# Zynq_processing_system.net
KiCad netlist of a schematic drawn in Altium Designer
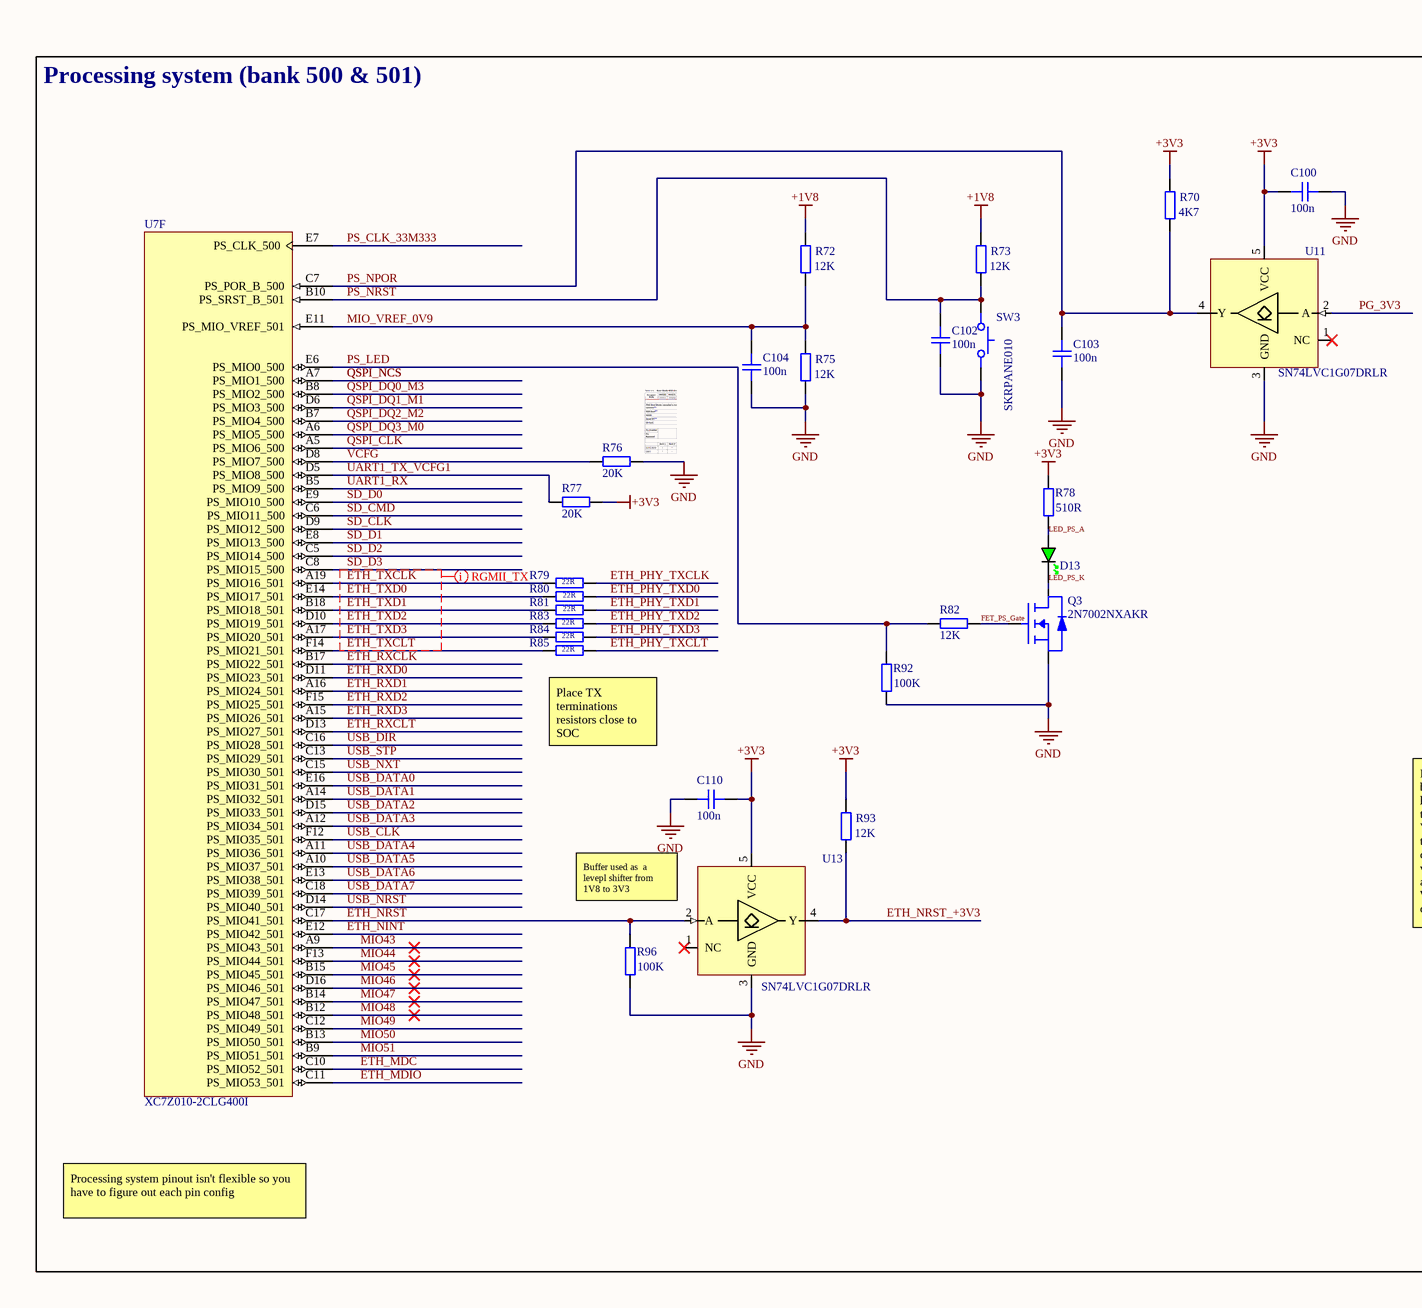
[diagram p0: Zynq processing system (PS).SchDoc, left]
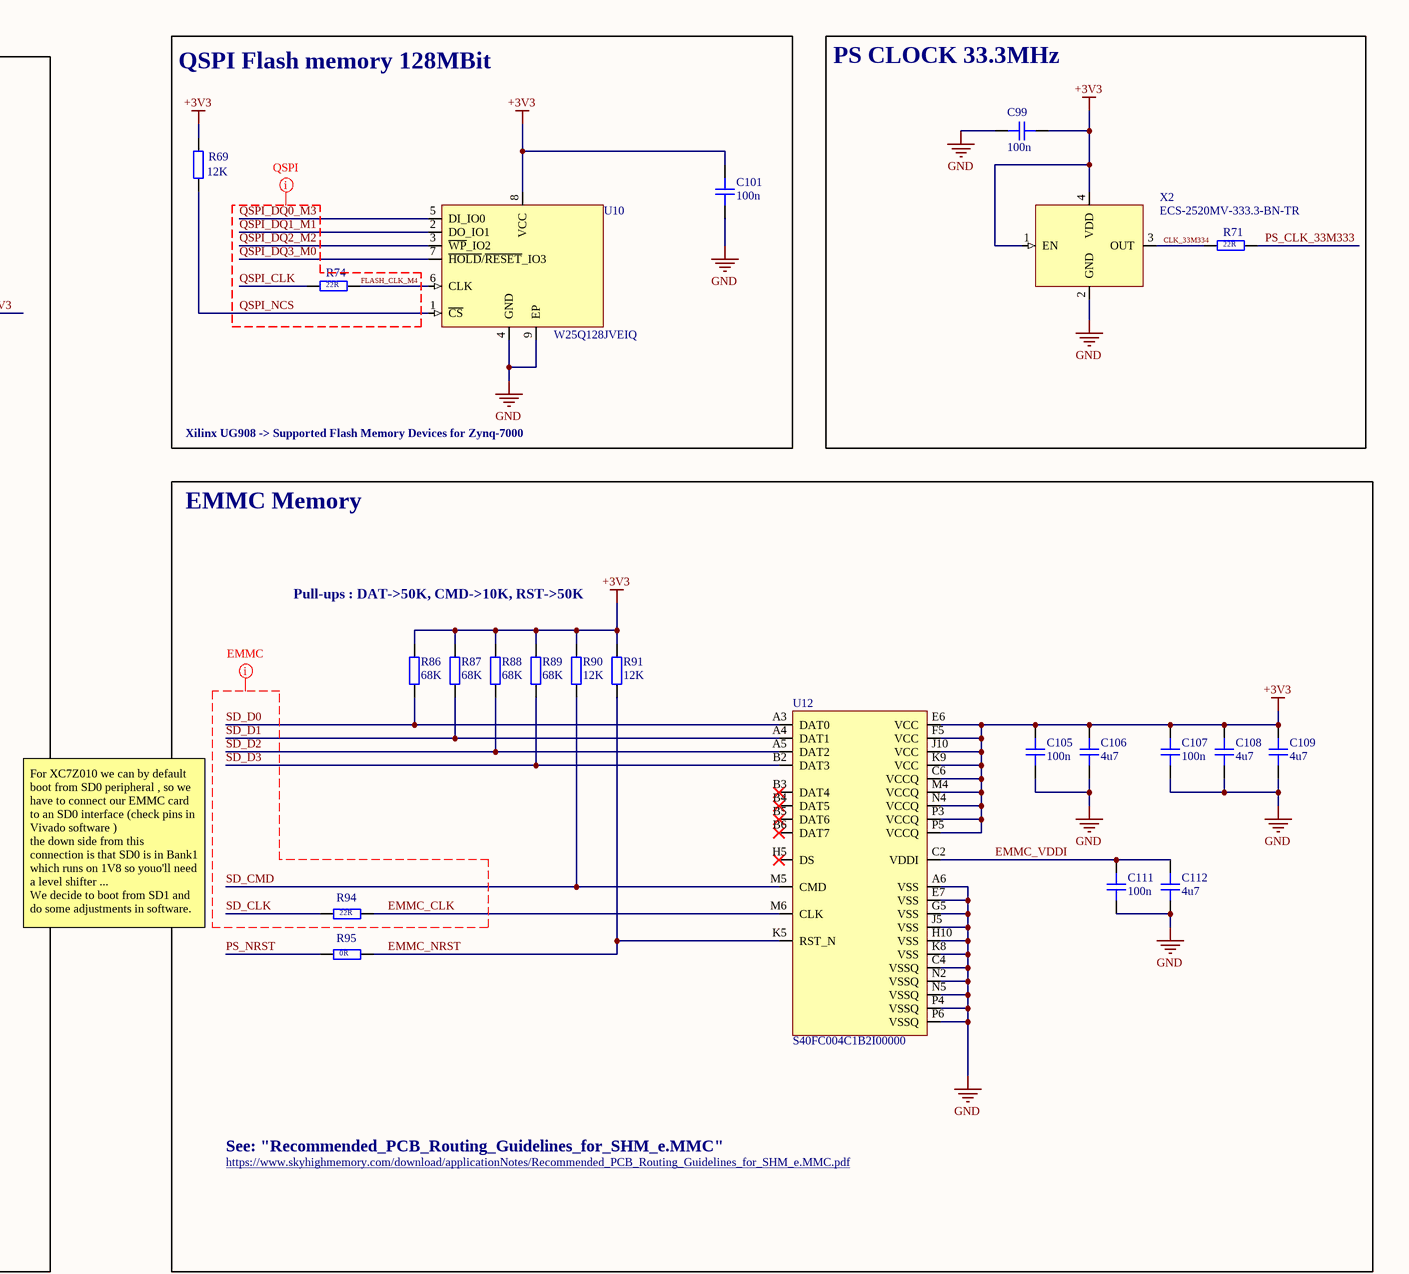
[diagram p1: Zynq processing system (PS).SchDoc, right]

(export (version "E")
  (design (tool "Eeschema 10.0.6"))
  (components
    (comp (ref "C99")
      (value "100n")
      (footprint "CAP_0402")
      (description "Capacitor SMD 0402")
      (libsource (lib "Schematic-Lib-PhilsLab") (part "CAP_0402"))
    )
    (comp (ref "C100")
      (value "100n")
      (footprint "CAP_0402")
      (description "Capacitor SMD 0402")
      (libsource (lib "Schematic-Lib-PhilsLab") (part "CAP_0402"))
    )
    (comp (ref "C101")
      (value "100n")
      (footprint "CAP_0402")
      (description "Capacitor SMD 0402")
      (libsource (lib "Schematic-Lib-PhilsLab") (part "CAP_0402"))
    )
    (comp (ref "C102")
      (value "100n")
      (footprint "CAP_0402")
      (description "Capacitor SMD 0402")
      (libsource (lib "Schematic-Lib-PhilsLab") (part "CAP_0402"))
    )
    (comp (ref "C103")
      (value "100n")
      (footprint "CAP_0402")
      (description "Capacitor SMD 0402")
      (libsource (lib "Schematic-Lib-PhilsLab") (part "CAP_0402"))
    )
    (comp (ref "C104")
      (value "100n")
      (footprint "CAP_0402")
      (description "Capacitor SMD 0402")
      (libsource (lib "Schematic-Lib-PhilsLab") (part "CAP_0402"))
    )
    (comp (ref "C105")
      (value "100n")
      (footprint "CAP_0402")
      (description "Capacitor SMD 0402")
      (libsource (lib "Schematic-Lib-PhilsLab") (part "CAP_0402"))
    )
    (comp (ref "C106")
      (value "4u7")
      (footprint "CAP_0402")
      (description "Capacitor SMD 0402")
      (libsource (lib "Schematic-Lib-PhilsLab") (part "CAP_0402"))
    )
    (comp (ref "C107")
      (value "100n")
      (footprint "CAP_0402")
      (description "Capacitor SMD 0402")
      (libsource (lib "Schematic-Lib-PhilsLab") (part "CAP_0402"))
    )
    (comp (ref "C108")
      (value "4u7")
      (footprint "CAP_0402")
      (description "Capacitor SMD 0402")
      (libsource (lib "Schematic-Lib-PhilsLab") (part "CAP_0402"))
    )
    (comp (ref "C109")
      (value "4u7")
      (footprint "CAP_0402")
      (description "Capacitor SMD 0402")
      (libsource (lib "Schematic-Lib-PhilsLab") (part "CAP_0402"))
    )
    (comp (ref "C110")
      (value "100n")
      (footprint "CAP_0402")
      (description "Capacitor SMD 0402")
      (libsource (lib "Schematic-Lib-PhilsLab") (part "CAP_0402"))
    )
    (comp (ref "C111")
      (value "100n")
      (footprint "CAP_0402")
      (description "Capacitor SMD 0402")
      (libsource (lib "Schematic-Lib-PhilsLab") (part "CAP_0402"))
    )
    (comp (ref "C112")
      (value "4u7")
      (footprint "CAP_0402")
      (description "Capacitor SMD 0402")
      (libsource (lib "Schematic-Lib-PhilsLab") (part "CAP_0402"))
    )
    (comp (ref "D13")
      (value "GREEN")
      (footprint "LED_0402_GREEN")
      (description "LED 0402 GREEN SMD")
      (libsource (lib "Schematic-Lib-PhilsLab") (part "LED_0402_GREEN"))
    )
    (comp (ref "Q3")
      (value "2N7002NXAKR")
      (footprint "SSM3J338R,LF-SOT23-F")
      (description "MOSFET N-Channel Vds=60V Id=300mA with ESD Protection")
      (fields (field (name "MANUFACTURER") "Nexperia"))
      (libsource (lib "Schematic-Lib-PhilsLab") (part "2N7002NXAKR"))
    )
    (comp (ref "R69")
      (value "12K")
      (footprint "RES_0402")
      (description "Resistor SMD 0402")
      (fields (field (name "Comment") "R0402"))
      (libsource (lib "Schematic-Lib-PhilsLab") (part "RES_0402"))
    )
    (comp (ref "R70")
      (value "4K7")
      (footprint "RES_0402")
      (description "Resistor SMD 0402")
      (fields (field (name "Comment") "R0402"))
      (libsource (lib "Schematic-Lib-PhilsLab") (part "RES_0402"))
    )
    (comp (ref "R71")
      (value "22R")
      (footprint "RES_0402")
      (description "Resistor SMD 0402")
      (fields (field (name "Comment") "R0402"))
      (libsource (lib "Schematic-Lib-PhilsLab") (part "RES_0402"))
    )
    (comp (ref "R72")
      (value "12K")
      (footprint "RES_0402")
      (description "Resistor SMD 0402")
      (fields (field (name "Comment") "R0402"))
      (libsource (lib "Schematic-Lib-PhilsLab") (part "RES_0402"))
    )
    (comp (ref "R73")
      (value "12K")
      (footprint "RES_0402")
      (description "Resistor SMD 0402")
      (fields (field (name "Comment") "R0402"))
      (libsource (lib "Schematic-Lib-PhilsLab") (part "RES_0402"))
    )
    (comp (ref "R74")
      (value "22R")
      (footprint "RES_0402")
      (description "Resistor SMD 0402")
      (fields (field (name "Comment") "R0402"))
      (libsource (lib "Schematic-Lib-PhilsLab") (part "RES_0402"))
    )
    (comp (ref "R75")
      (value "12K")
      (footprint "RES_0402")
      (description "Resistor SMD 0402")
      (fields (field (name "Comment") "R0402"))
      (libsource (lib "Schematic-Lib-PhilsLab") (part "RES_0402"))
    )
    (comp (ref "R76")
      (value "20K")
      (footprint "RES_0402")
      (description "Resistor SMD 0402")
      (fields (field (name "Comment") "R0402"))
      (libsource (lib "Schematic-Lib-PhilsLab") (part "RES_0402"))
    )
    (comp (ref "R77")
      (value "20K")
      (footprint "RES_0402")
      (description "Resistor SMD 0402")
      (fields (field (name "Comment") "R0402"))
      (libsource (lib "Schematic-Lib-PhilsLab") (part "RES_0402"))
    )
    (comp (ref "R78")
      (value "510R")
      (footprint "RES_0402")
      (description "Resistor SMD 0402")
      (fields (field (name "Comment") "R0402"))
      (libsource (lib "Schematic-Lib-PhilsLab") (part "RES_0402"))
    )
    (comp (ref "R79")
      (value "22R")
      (footprint "RES_0402")
      (description "Resistor SMD 0402")
      (fields (field (name "Comment") "R0402"))
      (libsource (lib "Schematic-Lib-PhilsLab") (part "RES_0402"))
    )
    (comp (ref "R80")
      (value "22R")
      (footprint "RES_0402")
      (description "Resistor SMD 0402")
      (fields (field (name "Comment") "R0402"))
      (libsource (lib "Schematic-Lib-PhilsLab") (part "RES_0402"))
    )
    (comp (ref "R81")
      (value "22R")
      (footprint "RES_0402")
      (description "Resistor SMD 0402")
      (fields (field (name "Comment") "R0402"))
      (libsource (lib "Schematic-Lib-PhilsLab") (part "RES_0402"))
    )
    (comp (ref "R82")
      (value "12K")
      (footprint "RES_0402")
      (description "Resistor SMD 0402")
      (fields (field (name "Comment") "R0402"))
      (libsource (lib "Schematic-Lib-PhilsLab") (part "RES_0402"))
    )
    (comp (ref "R83")
      (value "22R")
      (footprint "RES_0402")
      (description "Resistor SMD 0402")
      (fields (field (name "Comment") "R0402"))
      (libsource (lib "Schematic-Lib-PhilsLab") (part "RES_0402"))
    )
    (comp (ref "R84")
      (value "22R")
      (footprint "RES_0402")
      (description "Resistor SMD 0402")
      (fields (field (name "Comment") "R0402"))
      (libsource (lib "Schematic-Lib-PhilsLab") (part "RES_0402"))
    )
    (comp (ref "R85")
      (value "22R")
      (footprint "RES_0402")
      (description "Resistor SMD 0402")
      (fields (field (name "Comment") "R0402"))
      (libsource (lib "Schematic-Lib-PhilsLab") (part "RES_0402"))
    )
    (comp (ref "R86")
      (value "68K")
      (footprint "RES_0402")
      (description "Resistor SMD 0402")
      (fields (field (name "Comment") "R0402"))
      (libsource (lib "Schematic-Lib-PhilsLab") (part "RES_0402"))
    )
    (comp (ref "R87")
      (value "68K")
      (footprint "RES_0402")
      (description "Resistor SMD 0402")
      (fields (field (name "Comment") "R0402"))
      (libsource (lib "Schematic-Lib-PhilsLab") (part "RES_0402"))
    )
    (comp (ref "R88")
      (value "68K")
      (footprint "RES_0402")
      (description "Resistor SMD 0402")
      (fields (field (name "Comment") "R0402"))
      (libsource (lib "Schematic-Lib-PhilsLab") (part "RES_0402"))
    )
    (comp (ref "R89")
      (value "68K")
      (footprint "RES_0402")
      (description "Resistor SMD 0402")
      (fields (field (name "Comment") "R0402"))
      (libsource (lib "Schematic-Lib-PhilsLab") (part "RES_0402"))
    )
    (comp (ref "R90")
      (value "12K")
      (footprint "RES_0402")
      (description "Resistor SMD 0402")
      (fields (field (name "Comment") "R0402"))
      (libsource (lib "Schematic-Lib-PhilsLab") (part "RES_0402"))
    )
    (comp (ref "R91")
      (value "12K")
      (footprint "RES_0402")
      (description "Resistor SMD 0402")
      (fields (field (name "Comment") "R0402"))
      (libsource (lib "Schematic-Lib-PhilsLab") (part "RES_0402"))
    )
    (comp (ref "R92")
      (value "100K")
      (footprint "RES_0402")
      (description "Resistor SMD 0402")
      (fields (field (name "Comment") "R0402"))
      (libsource (lib "Schematic-Lib-PhilsLab") (part "RES_0402"))
    )
    (comp (ref "R93")
      (value "12K")
      (footprint "RES_0402")
      (description "Resistor SMD 0402")
      (fields (field (name "Comment") "R0402"))
      (libsource (lib "Schematic-Lib-PhilsLab") (part "RES_0402"))
    )
    (comp (ref "R94")
      (value "22R")
      (footprint "RES_0402")
      (description "Resistor SMD 0402")
      (fields (field (name "Comment") "R0402"))
      (libsource (lib "Schematic-Lib-PhilsLab") (part "RES_0402"))
    )
    (comp (ref "R95")
      (value "0R")
      (footprint "RES_0402")
      (description "Resistor SMD 0402")
      (fields (field (name "Comment") "R0402"))
      (libsource (lib "Schematic-Lib-PhilsLab") (part "RES_0402"))
    )
    (comp (ref "R96")
      (value "100K")
      (footprint "RES_0402")
      (description "Resistor SMD 0402")
      (fields (field (name "Comment") "R0402"))
      (libsource (lib "Schematic-Lib-PhilsLab") (part "RES_0402"))
    )
    (comp (ref "SW3")
      (value "SKRPANE010")
      (footprint "SKRPANE010")
      (description "Tactile Switch SMD SPST")
      (fields (field (name "MANUFACTURER") "Alps Alpine"))
      (libsource (lib "Schematic-Lib-PhilsLab") (part "SKRPANE010"))
    )
    (comp (ref "U7")
      (value "XC7Z010-2CLG400I")
      (footprint "BGA400C80P20X20_1700X1700X160N")
      (libsource (lib "Zynq_SOM") (part "XC7Z010-2CLG400I"))
    )
    (comp (ref "U10")
      (value "W25Q128JVEIQ")
      (footprint "WSON-8-8X6")
      (description "3V 128M-BIT SERIAL FLASH MEMORY WITH DUAL/QUAD SPI & QPI & DTR WSON-8")
      (fields (field (name "MANUFACTURER") "Winbond"))
      (libsource (lib "Schematic-Lib-PhilsLab") (part "W25Q128JVEIQ"))
    )
    (comp (ref "U11")
      (value "SN74LVC1G07DRLR")
      (footprint "SOT-5")
      (description "Single Buffer/Driver With Open-Drain Output")
      (fields (field (name "MANUFACTURER") "Texas Instruments"))
      (libsource (lib "Schematic-Lib-PhilsLab") (part "SN74LVC1G07DRLR"))
    )
    (comp (ref "U12")
      (value "S40FC004C1B2I00000")
      (footprint "VFBGA153-9.0x7.5x0.8")
      (description "eMMC MLC Memory 4GB 3V3")
      (fields (field (name "MANUFACTURER") "SkyHigh Memory"))
      (libsource (lib "Schematic-Lib-PhilsLab") (part "S40FC004C1B2I00000"))
    )
    (comp (ref "U13")
      (value "SN74LVC1G07DRLR")
      (footprint "SOT-5")
      (description "Single Buffer/Driver With Open-Drain Output")
      (fields (field (name "MANUFACTURER") "Texas Instruments"))
      (libsource (lib "") (part "SN74LVC1G07DRLR_1"))
    )
    (comp (ref "X2")
      (value "ECS-2520MV-333.3-BN-TR")
      (footprint "XTAL_2520")
      (fields
        (field (name "MANUFACTURER") "ECS")
        (field (name "MANUFACTURER PART NUMBER") "ECS-2520MV-130-BN-TR")
      )
      (libsource (lib "Schematic-Lib-PhilsLab") (part "ECS-2520MV-130-BN-TR"))
    )
  )
  (nets
    (net (code "1") (name "+1V8") (class "Default")
      (node (ref "R72") (pin "2") (pinfunction "2_2") (pintype "passive"))
      (node (ref "R73") (pin "2") (pinfunction "2_2") (pintype "passive"))
    )
    (net (code "2") (name "+3V3") (class "Default")
      (node (ref "C100") (pin "2") (pinfunction "2_2") (pintype "passive"))
      (node (ref "C101") (pin "1") (pinfunction "1_1") (pintype "passive"))
      (node (ref "C105") (pin "1") (pinfunction "1_1") (pintype "passive"))
      (node (ref "C106") (pin "1") (pinfunction "1_1") (pintype "passive"))
      (node (ref "C107") (pin "1") (pinfunction "1_1") (pintype "passive"))
      (node (ref "C108") (pin "1") (pinfunction "1_1") (pintype "passive"))
      (node (ref "C109") (pin "1") (pinfunction "1_1") (pintype "passive"))
      (node (ref "C110") (pin "2") (pinfunction "2_2") (pintype "passive"))
      (node (ref "C99") (pin "1") (pinfunction "1_1") (pintype "passive"))
      (node (ref "R69") (pin "2") (pinfunction "2_2") (pintype "passive"))
      (node (ref "R70") (pin "2") (pinfunction "2_2") (pintype "passive"))
      (node (ref "R77") (pin "1") (pinfunction "1_1") (pintype "passive"))
      (node (ref "R78") (pin "1") (pinfunction "1_1") (pintype "passive"))
      (node (ref "R86") (pin "1") (pinfunction "1_1") (pintype "passive"))
      (node (ref "R87") (pin "1") (pinfunction "1_1") (pintype "passive"))
      (node (ref "R88") (pin "1") (pinfunction "1_1") (pintype "passive"))
      (node (ref "R89") (pin "1") (pinfunction "1_1") (pintype "passive"))
      (node (ref "R90") (pin "1") (pinfunction "1_1") (pintype "passive"))
      (node (ref "R91") (pin "1") (pinfunction "1_1") (pintype "passive"))
      (node (ref "R93") (pin "2") (pinfunction "2_2") (pintype "passive"))
      (node (ref "U10") (pin "8") (pinfunction "VCC_8") (pintype "power_in"))
      (node (ref "U11") (pin "5") (pinfunction "VCC_5") (pintype "power_in"))
      (node (ref "U12") (pin "C6") (pinfunction "VCCQ_C6") (pintype "passive"))
      (node (ref "U12") (pin "E6") (pinfunction "VCC_E6") (pintype "passive"))
      (node (ref "U12") (pin "F5") (pinfunction "VCC_F5") (pintype "passive"))
      (node (ref "U12") (pin "J10") (pinfunction "VCC_J10") (pintype "passive"))
      (node (ref "U12") (pin "K9") (pinfunction "VCC_K9") (pintype "passive"))
      (node (ref "U12") (pin "M4") (pinfunction "VCCQ_M4") (pintype "passive"))
      (node (ref "U12") (pin "N4") (pinfunction "VCCQ_N4") (pintype "passive"))
      (node (ref "U12") (pin "P3") (pinfunction "VCCQ_P3") (pintype "passive"))
      (node (ref "U12") (pin "P5") (pinfunction "VCCQ_P5") (pintype "passive"))
      (node (ref "U13") (pin "5") (pinfunction "VCC_5") (pintype "power_in"))
      (node (ref "X2") (pin "1") (pinfunction "EN_1") (pintype "input"))
      (node (ref "X2") (pin "4") (pinfunction "VDD_4") (pintype "power_in"))
    )
    (net (code "3") (name "/CLK_33M334") (class "Default")
      (node (ref "R71") (pin "2") (pinfunction "2_2") (pintype "passive"))
      (node (ref "X2") (pin "3") (pinfunction "OUT_3") (pintype "passive"))
    )
    (net (code "4") (name "/EMMC_CLK") (class "Default")
      (node (ref "R94") (pin "1") (pinfunction "1_1") (pintype "passive"))
      (node (ref "U12") (pin "M6") (pinfunction "CLK_M6") (pintype "passive"))
    )
    (net (code "5") (name "/EMMC_NRST") (class "Default")
      (node (ref "R91") (pin "2") (pinfunction "2_2") (pintype "passive"))
      (node (ref "R95") (pin "1") (pinfunction "1_1") (pintype "passive"))
      (node (ref "U12") (pin "K5") (pinfunction "RST_N_K5") (pintype "passive"))
    )
    (net (code "6") (name "/EMMC_VDDI") (class "Default")
      (node (ref "C111") (pin "1") (pinfunction "1_1") (pintype "passive"))
      (node (ref "C112") (pin "1") (pinfunction "1_1") (pintype "passive"))
      (node (ref "U12") (pin "C2") (pinfunction "VDDI_C2") (pintype "passive"))
    )
    (net (code "7") (name "/ETH_MDC") (class "Default")
      (node (ref "U7") (pin "C10") (pinfunction "PS_MIO52_501_C10") (pintype "bidirectional"))
    )
    (net (code "8") (name "/ETH_MDIO") (class "Default")
      (node (ref "U7") (pin "C11") (pinfunction "PS_MIO53_501_C11") (pintype "bidirectional"))
    )
    (net (code "9") (name "/ETH_NINT") (class "Default")
      (node (ref "U7") (pin "E12") (pinfunction "PS_MIO42_501_E12") (pintype "bidirectional"))
    )
    (net (code "10") (name "/ETH_NRST") (class "Default")
      (node (ref "R96") (pin "1") (pinfunction "1_1") (pintype "passive"))
      (node (ref "U13") (pin "2") (pinfunction "A_2") (pintype "input"))
      (node (ref "U7") (pin "C17") (pinfunction "PS_MIO41_501_C17") (pintype "bidirectional"))
    )
    (net (code "11") (name "/ETH_NRST_+3V3") (class "Default")
      (node (ref "R93") (pin "1") (pinfunction "1_1") (pintype "passive"))
      (node (ref "U13") (pin "4") (pinfunction "Y_4") (pintype "open_collector"))
    )
    (net (code "12") (name "/ETH_PHY_TXCLK") (class "Default")
      (node (ref "R79") (pin "1") (pinfunction "1_1") (pintype "passive"))
    )
    (net (code "13") (name "/ETH_PHY_TXCLT") (class "Default")
      (node (ref "R85") (pin "1") (pinfunction "1_1") (pintype "passive"))
    )
    (net (code "14") (name "/ETH_PHY_TXD0") (class "Default")
      (node (ref "R80") (pin "1") (pinfunction "1_1") (pintype "passive"))
    )
    (net (code "15") (name "/ETH_PHY_TXD1") (class "Default")
      (node (ref "R81") (pin "1") (pinfunction "1_1") (pintype "passive"))
    )
    (net (code "16") (name "/ETH_PHY_TXD2") (class "Default")
      (node (ref "R83") (pin "1") (pinfunction "1_1") (pintype "passive"))
    )
    (net (code "17") (name "/ETH_PHY_TXD3") (class "Default")
      (node (ref "R84") (pin "1") (pinfunction "1_1") (pintype "passive"))
    )
    (net (code "18") (name "/ETH_RXCLK") (class "Default")
      (node (ref "U7") (pin "B17") (pinfunction "PS_MIO22_501_B17") (pintype "bidirectional"))
    )
    (net (code "19") (name "/ETH_RXCLT") (class "Default")
      (node (ref "U7") (pin "D13") (pinfunction "PS_MIO27_501_D13") (pintype "bidirectional"))
    )
    (net (code "20") (name "/ETH_RXD0") (class "Default")
      (node (ref "U7") (pin "D11") (pinfunction "PS_MIO23_501_D11") (pintype "bidirectional"))
    )
    (net (code "21") (name "/ETH_RXD1") (class "Default")
      (node (ref "U7") (pin "A16") (pinfunction "PS_MIO24_501_A16") (pintype "bidirectional"))
    )
    (net (code "22") (name "/ETH_RXD2") (class "Default")
      (node (ref "U7") (pin "F15") (pinfunction "PS_MIO25_501_F15") (pintype "bidirectional"))
    )
    (net (code "23") (name "/ETH_RXD3") (class "Default")
      (node (ref "U7") (pin "A15") (pinfunction "PS_MIO26_501_A15") (pintype "bidirectional"))
    )
    (net (code "24") (name "/ETH_TXCLK") (class "Default")
      (node (ref "R79") (pin "2") (pinfunction "2_2") (pintype "passive"))
      (node (ref "U7") (pin "A19") (pinfunction "PS_MIO16_501_A19") (pintype "bidirectional"))
    )
    (net (code "25") (name "/ETH_TXCLT") (class "Default")
      (node (ref "R85") (pin "2") (pinfunction "2_2") (pintype "passive"))
      (node (ref "U7") (pin "F14") (pinfunction "PS_MIO21_501_F14") (pintype "bidirectional"))
    )
    (net (code "26") (name "/ETH_TXD0") (class "Default")
      (node (ref "R80") (pin "2") (pinfunction "2_2") (pintype "passive"))
      (node (ref "U7") (pin "E14") (pinfunction "PS_MIO17_501_E14") (pintype "bidirectional"))
    )
    (net (code "27") (name "/ETH_TXD1") (class "Default")
      (node (ref "R81") (pin "2") (pinfunction "2_2") (pintype "passive"))
      (node (ref "U7") (pin "B18") (pinfunction "PS_MIO18_501_B18") (pintype "bidirectional"))
    )
    (net (code "28") (name "/ETH_TXD2") (class "Default")
      (node (ref "R83") (pin "2") (pinfunction "2_2") (pintype "passive"))
      (node (ref "U7") (pin "D10") (pinfunction "PS_MIO19_501_D10") (pintype "bidirectional"))
    )
    (net (code "29") (name "/ETH_TXD3") (class "Default")
      (node (ref "R84") (pin "2") (pinfunction "2_2") (pintype "passive"))
      (node (ref "U7") (pin "A17") (pinfunction "PS_MIO20_501_A17") (pintype "bidirectional"))
    )
    (net (code "30") (name "/FET_PS_Gate") (class "Default")
      (node (ref "Q3") (pin "G") (pinfunction "G_G") (pintype "passive"))
      (node (ref "R82") (pin "1") (pinfunction "1_1") (pintype "passive"))
    )
    (net (code "31") (name "/FLASH_CLK_M4") (class "Default")
      (node (ref "R74") (pin "1") (pinfunction "1_1") (pintype "passive"))
      (node (ref "U10") (pin "6") (pinfunction "CLK_6") (pintype "input"))
    )
    (net (code "32") (name "/LED_PS_A") (class "Default")
      (node (ref "D13") (pin "A") (pinfunction "A_A") (pintype "passive"))
      (node (ref "R78") (pin "2") (pinfunction "2_2") (pintype "passive"))
    )
    (net (code "33") (name "/LED_PS_K") (class "Default")
      (node (ref "D13") (pin "K") (pinfunction "K_K") (pintype "passive"))
      (node (ref "Q3") (pin "D") (pinfunction "D_D") (pintype "passive"))
    )
    (net (code "34") (name "/MIO43") (class "Default")
      (node (ref "U7") (pin "A9") (pinfunction "PS_MIO43_501_A9") (pintype "bidirectional"))
    )
    (net (code "35") (name "/MIO44") (class "Default")
      (node (ref "U7") (pin "F13") (pinfunction "PS_MIO44_501_F13") (pintype "bidirectional"))
    )
    (net (code "36") (name "/MIO45") (class "Default")
      (node (ref "U7") (pin "B15") (pinfunction "PS_MIO45_501_B15") (pintype "bidirectional"))
    )
    (net (code "37") (name "/MIO46") (class "Default")
      (node (ref "U7") (pin "D16") (pinfunction "PS_MIO46_501_D16") (pintype "bidirectional"))
    )
    (net (code "38") (name "/MIO47") (class "Default")
      (node (ref "U7") (pin "B14") (pinfunction "PS_MIO47_501_B14") (pintype "bidirectional"))
    )
    (net (code "39") (name "/MIO48") (class "Default")
      (node (ref "U7") (pin "B12") (pinfunction "PS_MIO48_501_B12") (pintype "bidirectional"))
    )
    (net (code "40") (name "/MIO49") (class "Default")
      (node (ref "U7") (pin "C12") (pinfunction "PS_MIO49_501_C12") (pintype "bidirectional"))
    )
    (net (code "41") (name "/MIO50") (class "Default")
      (node (ref "U7") (pin "B13") (pinfunction "PS_MIO50_501_B13") (pintype "bidirectional"))
    )
    (net (code "42") (name "/MIO51") (class "Default")
      (node (ref "U7") (pin "B9") (pinfunction "PS_MIO51_501_B9") (pintype "bidirectional"))
    )
    (net (code "43") (name "/MIO_VREF_0V9") (class "Default")
      (node (ref "C104") (pin "1") (pinfunction "1_1") (pintype "passive"))
      (node (ref "R72") (pin "1") (pinfunction "1_1") (pintype "passive"))
      (node (ref "R75") (pin "2") (pinfunction "2_2") (pintype "passive"))
      (node (ref "U7") (pin "E11") (pinfunction "PS_MIO_VREF_501_E11") (pintype "input"))
    )
    (net (code "44") (name "/PG_3V3") (class "Default")
      (node (ref "U11") (pin "2") (pinfunction "A_2") (pintype "input"))
    )
    (net (code "45") (name "/PS_CLK_33M333") (class "Default")
      (node (ref "R71") (pin "1") (pinfunction "1_1") (pintype "passive"))
      (node (ref "U7") (pin "E7") (pinfunction "PS_CLK_500_E7") (pintype "passive"))
    )
    (net (code "46") (name "/PS_LED") (class "Default")
      (node (ref "R82") (pin "2") (pinfunction "2_2") (pintype "passive"))
      (node (ref "R92") (pin "1") (pinfunction "1_1") (pintype "passive"))
      (node (ref "U7") (pin "E6") (pinfunction "PS_MIO0_500_E6") (pintype "bidirectional"))
    )
    (net (code "47") (name "/PS_NPOR") (class "Default")
      (node (ref "C103") (pin "1") (pinfunction "1_1") (pintype "passive"))
      (node (ref "R70") (pin "1") (pinfunction "1_1") (pintype "passive"))
      (node (ref "U11") (pin "4") (pinfunction "Y_4") (pintype "open_collector"))
      (node (ref "U7") (pin "C7") (pinfunction "PS_POR_B_500_C7") (pintype "input"))
    )
    (net (code "48") (name "/PS_NRST") (class "Default")
      (node (ref "C102") (pin "1") (pinfunction "1_1") (pintype "passive"))
      (node (ref "R73") (pin "1") (pinfunction "1_1") (pintype "passive"))
      (node (ref "R95") (pin "2") (pinfunction "2_2") (pintype "passive"))
      (node (ref "SW3") (pin "34") (pintype "passive"))
      (node (ref "U7") (pin "B10") (pinfunction "PS_SRST_B_501_B10") (pintype "input"))
    )
    (net (code "49") (name "/QSPI_CLK") (class "Default")
      (node (ref "R74") (pin "2") (pinfunction "2_2") (pintype "passive"))
      (node (ref "U7") (pin "A5") (pinfunction "PS_MIO6_500_A5") (pintype "bidirectional"))
    )
    (net (code "50") (name "/QSPI_DQ0_M3") (class "Default")
      (node (ref "U10") (pin "5") (pinfunction "DI_IO0_5") (pintype "bidirectional"))
      (node (ref "U7") (pin "B8") (pinfunction "PS_MIO2_500_B8") (pintype "bidirectional"))
    )
    (net (code "51") (name "/QSPI_DQ1_M1") (class "Default")
      (node (ref "U10") (pin "2") (pinfunction "DO_IO1_2") (pintype "bidirectional"))
      (node (ref "U7") (pin "D6") (pinfunction "PS_MIO3_500_D6") (pintype "bidirectional"))
    )
    (net (code "52") (name "/QSPI_DQ2_M2") (class "Default")
      (node (ref "U10") (pin "3") (pinfunction "~{WP}_IO2_3") (pintype "bidirectional"))
      (node (ref "U7") (pin "B7") (pinfunction "PS_MIO4_500_B7") (pintype "bidirectional"))
    )
    (net (code "53") (name "/QSPI_DQ3_M0") (class "Default")
      (node (ref "U10") (pin "7") (pinfunction "~{HOLD}/~{RESET}_IO3_7") (pintype "bidirectional"))
      (node (ref "U7") (pin "A6") (pinfunction "PS_MIO5_500_A6") (pintype "bidirectional"))
    )
    (net (code "54") (name "/QSPI_NCS") (class "Default")
      (node (ref "R69") (pin "1") (pinfunction "1_1") (pintype "passive"))
      (node (ref "U10") (pin "1") (pinfunction "~{CS}_1") (pintype "input"))
      (node (ref "U7") (pin "A7") (pinfunction "PS_MIO1_500_A7") (pintype "bidirectional"))
    )
    (net (code "55") (name "/SD_CLK") (class "Default")
      (node (ref "R94") (pin "2") (pinfunction "2_2") (pintype "passive"))
      (node (ref "U7") (pin "D9") (pinfunction "PS_MIO12_500_D9") (pintype "bidirectional"))
    )
    (net (code "56") (name "/SD_CMD") (class "Default")
      (node (ref "R90") (pin "2") (pinfunction "2_2") (pintype "passive"))
      (node (ref "U12") (pin "M5") (pinfunction "CMD_M5") (pintype "passive"))
      (node (ref "U7") (pin "C6") (pinfunction "PS_MIO11_500_C6") (pintype "bidirectional"))
    )
    (net (code "57") (name "/SD_D0") (class "Default")
      (node (ref "R86") (pin "2") (pinfunction "2_2") (pintype "passive"))
      (node (ref "U12") (pin "A3") (pinfunction "DAT0_A3") (pintype "passive"))
      (node (ref "U7") (pin "E9") (pinfunction "PS_MIO10_500_E9") (pintype "bidirectional"))
    )
    (net (code "58") (name "/SD_D1") (class "Default")
      (node (ref "R87") (pin "2") (pinfunction "2_2") (pintype "passive"))
      (node (ref "U12") (pin "A4") (pinfunction "DAT1_A4") (pintype "passive"))
      (node (ref "U7") (pin "E8") (pinfunction "PS_MIO13_500_E8") (pintype "bidirectional"))
    )
    (net (code "59") (name "/SD_D2") (class "Default")
      (node (ref "R88") (pin "2") (pinfunction "2_2") (pintype "passive"))
      (node (ref "U12") (pin "A5") (pinfunction "DAT2_A5") (pintype "passive"))
      (node (ref "U7") (pin "C5") (pinfunction "PS_MIO14_500_C5") (pintype "bidirectional"))
    )
    (net (code "60") (name "/SD_D3") (class "Default")
      (node (ref "R89") (pin "2") (pinfunction "2_2") (pintype "passive"))
      (node (ref "U12") (pin "B2") (pinfunction "DAT3_B2") (pintype "passive"))
      (node (ref "U7") (pin "C8") (pinfunction "PS_MIO15_500_C8") (pintype "bidirectional"))
    )
    (net (code "61") (name "/UART1_RX") (class "Default")
      (node (ref "U7") (pin "B5") (pinfunction "PS_MIO9_500_B5") (pintype "bidirectional"))
    )
    (net (code "62") (name "/UART1_TX_VCFG1") (class "Default")
      (node (ref "R77") (pin "2") (pinfunction "2_2") (pintype "passive"))
      (node (ref "U7") (pin "D5") (pinfunction "PS_MIO8_500_D5") (pintype "bidirectional"))
    )
    (net (code "63") (name "/USB_CLK") (class "Default")
      (node (ref "U7") (pin "F12") (pinfunction "PS_MIO35_501_F12") (pintype "bidirectional"))
    )
    (net (code "64") (name "/USB_DATA0") (class "Default")
      (node (ref "U7") (pin "E16") (pinfunction "PS_MIO31_501_E16") (pintype "bidirectional"))
    )
    (net (code "65") (name "/USB_DATA1") (class "Default")
      (node (ref "U7") (pin "A14") (pinfunction "PS_MIO32_501_A14") (pintype "bidirectional"))
    )
    (net (code "66") (name "/USB_DATA2") (class "Default")
      (node (ref "U7") (pin "D15") (pinfunction "PS_MIO33_501_D15") (pintype "bidirectional"))
    )
    (net (code "67") (name "/USB_DATA3") (class "Default")
      (node (ref "U7") (pin "A12") (pinfunction "PS_MIO34_501_A12") (pintype "bidirectional"))
    )
    (net (code "68") (name "/USB_DATA4") (class "Default")
      (node (ref "U7") (pin "A11") (pinfunction "PS_MIO36_501_A11") (pintype "bidirectional"))
    )
    (net (code "69") (name "/USB_DATA5") (class "Default")
      (node (ref "U7") (pin "A10") (pinfunction "PS_MIO37_501_A10") (pintype "bidirectional"))
    )
    (net (code "70") (name "/USB_DATA6") (class "Default")
      (node (ref "U7") (pin "E13") (pinfunction "PS_MIO38_501_E13") (pintype "bidirectional"))
    )
    (net (code "71") (name "/USB_DATA7") (class "Default")
      (node (ref "U7") (pin "C18") (pinfunction "PS_MIO39_501_C18") (pintype "bidirectional"))
    )
    (net (code "72") (name "/USB_DIR") (class "Default")
      (node (ref "U7") (pin "C16") (pinfunction "PS_MIO28_501_C16") (pintype "bidirectional"))
    )
    (net (code "73") (name "/USB_NRST") (class "Default")
      (node (ref "U7") (pin "D14") (pinfunction "PS_MIO40_501_D14") (pintype "bidirectional"))
    )
    (net (code "74") (name "/USB_NXT") (class "Default")
      (node (ref "U7") (pin "C15") (pinfunction "PS_MIO30_501_C15") (pintype "bidirectional"))
    )
    (net (code "75") (name "/USB_STP") (class "Default")
      (node (ref "U7") (pin "C13") (pinfunction "PS_MIO29_501_C13") (pintype "bidirectional"))
    )
    (net (code "76") (name "/VCFG") (class "Default")
      (node (ref "R76") (pin "2") (pinfunction "2_2") (pintype "passive"))
      (node (ref "U7") (pin "D8") (pinfunction "PS_MIO7_500_D8") (pintype "bidirectional"))
    )
    (net (code "77") (name "GND") (class "Default")
      (node (ref "C100") (pin "1") (pinfunction "1_1") (pintype "passive"))
      (node (ref "C101") (pin "2") (pinfunction "2_2") (pintype "passive"))
      (node (ref "C102") (pin "2") (pinfunction "2_2") (pintype "passive"))
      (node (ref "C103") (pin "2") (pinfunction "2_2") (pintype "passive"))
      (node (ref "C104") (pin "2") (pinfunction "2_2") (pintype "passive"))
      (node (ref "C105") (pin "2") (pinfunction "2_2") (pintype "passive"))
      (node (ref "C106") (pin "2") (pinfunction "2_2") (pintype "passive"))
      (node (ref "C107") (pin "2") (pinfunction "2_2") (pintype "passive"))
      (node (ref "C108") (pin "2") (pinfunction "2_2") (pintype "passive"))
      (node (ref "C109") (pin "2") (pinfunction "2_2") (pintype "passive"))
      (node (ref "C110") (pin "1") (pinfunction "1_1") (pintype "passive"))
      (node (ref "C111") (pin "2") (pinfunction "2_2") (pintype "passive"))
      (node (ref "C112") (pin "2") (pinfunction "2_2") (pintype "passive"))
      (node (ref "C99") (pin "2") (pinfunction "2_2") (pintype "passive"))
      (node (ref "Q3") (pin "S") (pinfunction "S_S") (pintype "passive"))
      (node (ref "R75") (pin "1") (pinfunction "1_1") (pintype "passive"))
      (node (ref "R76") (pin "1") (pinfunction "1_1") (pintype "passive"))
      (node (ref "R92") (pin "2") (pinfunction "2_2") (pintype "passive"))
      (node (ref "R96") (pin "2") (pinfunction "2_2") (pintype "passive"))
      (node (ref "SW3") (pin "12") (pintype "passive"))
      (node (ref "U10") (pin "4") (pinfunction "GND_4") (pintype "power_in"))
      (node (ref "U10") (pin "9") (pinfunction "EP_9") (pintype "power_in"))
      (node (ref "U11") (pin "3") (pinfunction "GND_3") (pintype "power_in"))
      (node (ref "U12") (pin "A6") (pinfunction "VSS_A6") (pintype "passive"))
      (node (ref "U12") (pin "C4") (pinfunction "VSSQ_C4") (pintype "passive"))
      (node (ref "U12") (pin "E7") (pinfunction "VSS_E7") (pintype "passive"))
      (node (ref "U12") (pin "G5") (pinfunction "VSS_G5") (pintype "passive"))
      (node (ref "U12") (pin "H10") (pinfunction "VSS_H10") (pintype "passive"))
      (node (ref "U12") (pin "J5") (pinfunction "VSS_J5") (pintype "passive"))
      (node (ref "U12") (pin "K8") (pinfunction "VSS_K8") (pintype "passive"))
      (node (ref "U12") (pin "N2") (pinfunction "VSSQ_N2") (pintype "passive"))
      (node (ref "U12") (pin "N5") (pinfunction "VSSQ_N5") (pintype "passive"))
      (node (ref "U12") (pin "P4") (pinfunction "VSSQ_P4") (pintype "passive"))
      (node (ref "U12") (pin "P6") (pinfunction "VSSQ_P6") (pintype "passive"))
      (node (ref "U13") (pin "3") (pinfunction "GND_3") (pintype "power_in"))
      (node (ref "X2") (pin "2") (pinfunction "GND_2") (pintype "power_in"))
    )
    (net (code "78") (name "unconnected-(U11-NC-Pad1)") (class "Default")
      (node (ref "U11") (pin "1") (pinfunction "NC_1") (pintype "passive+no_connect"))
    )
    (net (code "79") (name "unconnected-(U12-DAT4-PadB3)") (class "Default")
      (node (ref "U12") (pin "B3") (pinfunction "DAT4_B3") (pintype "passive+no_connect"))
    )
    (net (code "80") (name "unconnected-(U12-DAT5-PadB4)") (class "Default")
      (node (ref "U12") (pin "B4") (pinfunction "DAT5_B4") (pintype "passive+no_connect"))
    )
    (net (code "81") (name "unconnected-(U12-DAT6-PadB5)") (class "Default")
      (node (ref "U12") (pin "B5") (pinfunction "DAT6_B5") (pintype "passive+no_connect"))
    )
    (net (code "82") (name "unconnected-(U12-DAT7-PadB6)") (class "Default")
      (node (ref "U12") (pin "B6") (pinfunction "DAT7_B6") (pintype "passive+no_connect"))
    )
    (net (code "83") (name "unconnected-(U12-DS-PadH5)") (class "Default")
      (node (ref "U12") (pin "H5") (pinfunction "DS_H5") (pintype "passive+no_connect"))
    )
    (net (code "84") (name "unconnected-(U13-NC-Pad1)") (class "Default")
      (node (ref "U13") (pin "1") (pinfunction "NC_1") (pintype "passive+no_connect"))
    )
  )
)
